# Isolator.net
KiCad netlist of a schematic drawn in Altium Designer
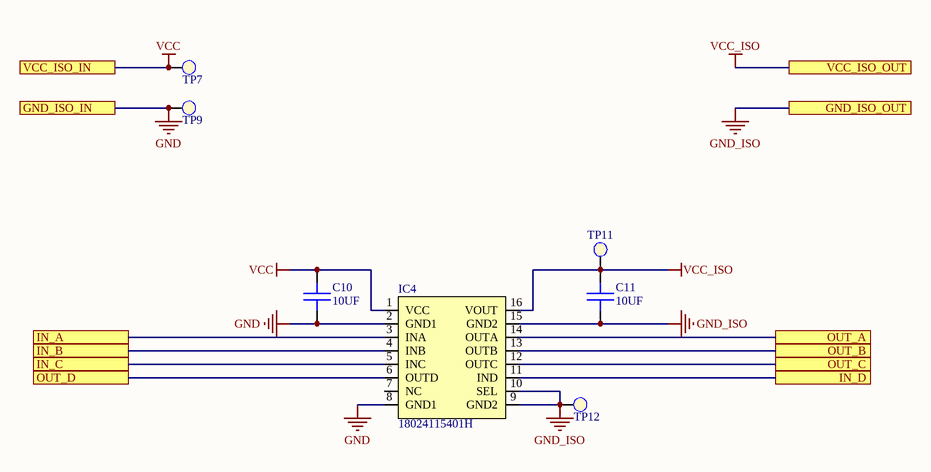
[diagram p0: Isolator.SchDoc]

(export (version "E")
  (design (tool "Eeschema 10.0.6"))
  (components
    (comp (ref "C10")
      (value "10UF")
      (footprint "c1206")
      (description "10UF, 16V, X7R, 1206")
      (fields
        (field (name "MANUFACTURER") "Samsung")
        (field (name "MANUFACTURER PART NUMBER") "CL31B106MOHNNNE")
      )
      (libsource (lib "Capacitor") (part "CL31B106MOHNNNE"))
    )
    (comp (ref "C11")
      (value "10UF")
      (footprint "c1206")
      (description "10UF, 16V, X7R, 1206")
      (fields
        (field (name "MANUFACTURER") "Samsung")
        (field (name "MANUFACTURER PART NUMBER") "CL31B106MOHNNNE")
      )
      (libsource (lib "Capacitor") (part "CL31B106MOHNNNE"))
    )
    (comp (ref "IC4")
      (value "18024115401H")
      (footprint "WPME-CDIP_SOIC-16WB")
      (description "WPME-CDIP Capacitive Digital Isolator Powered")
      (fields (field (name "MANUFACTURER") "Wurth Elektronik"))
      (libsource (lib "IntegratedCircuit") (part "18024115401H"))
    )
    (comp (ref "TP7")
      (value "TestPoint1")
      (footprint "SMD_1mmPoint")
      (description "test ölçüm noktası")
      (fields (field (name "MANUFACTURER") "NO BOM DEVICE"))
      (libsource (lib "Connectors") (part "TestPoint1"))
    )
    (comp (ref "TP9")
      (value "TestPoint1")
      (footprint "SMD_1mmPoint")
      (description "test ölçüm noktası")
      (fields (field (name "MANUFACTURER") "NO BOM DEVICE"))
      (libsource (lib "Connectors") (part "TestPoint1"))
    )
    (comp (ref "TP11")
      (value "TestPoint1")
      (footprint "SMD_1mmPoint")
      (description "test ölçüm noktası")
      (fields (field (name "MANUFACTURER") "NO BOM DEVICE"))
      (libsource (lib "Connectors") (part "TestPoint1"))
    )
    (comp (ref "TP12")
      (value "TestPoint1")
      (footprint "SMD_1mmPoint")
      (description "test ölçüm noktası")
      (fields (field (name "MANUFACTURER") "NO BOM DEVICE"))
      (libsource (lib "Connectors") (part "TestPoint1"))
    )
  )
  (nets
    (net (code "1") (name "/IN_A") (class "Default")
      (node (ref "IC4") (pin "3") (pinfunction "INA_3") (pintype "passive"))
    )
    (net (code "2") (name "/IN_B") (class "Default")
      (node (ref "IC4") (pin "4") (pinfunction "INB_4") (pintype "passive"))
    )
    (net (code "3") (name "/IN_C") (class "Default")
      (node (ref "IC4") (pin "5") (pinfunction "INC_5") (pintype "passive"))
    )
    (net (code "4") (name "/IN_D") (class "Default")
      (node (ref "IC4") (pin "11") (pinfunction "IND_11") (pintype "passive"))
    )
    (net (code "5") (name "/OUT_A") (class "Default")
      (node (ref "IC4") (pin "14") (pinfunction "OUTA_14") (pintype "passive"))
    )
    (net (code "6") (name "/OUT_B") (class "Default")
      (node (ref "IC4") (pin "13") (pinfunction "OUTB_13") (pintype "passive"))
    )
    (net (code "7") (name "/OUT_C") (class "Default")
      (node (ref "IC4") (pin "12") (pinfunction "OUTC_12") (pintype "passive"))
    )
    (net (code "8") (name "/OUT_D") (class "Default")
      (node (ref "IC4") (pin "6") (pinfunction "OUTD_6") (pintype "passive"))
    )
    (net (code "9") (name "GND") (class "Default")
      (node (ref "C10") (pin "1") (pintype "passive"))
      (node (ref "IC4") (pin "2") (pinfunction "GND1_2") (pintype "passive"))
      (node (ref "IC4") (pin "8") (pinfunction "GND1_8") (pintype "passive"))
      (node (ref "TP9") (pin "1") (pinfunction "1_1") (pintype "passive"))
    )
    (net (code "10") (name "GND_ISO") (class "Default")
      (node (ref "C11") (pin "1") (pintype "passive"))
      (node (ref "IC4") (pin "10") (pinfunction "SEL_10") (pintype "passive"))
      (node (ref "IC4") (pin "15") (pinfunction "GND2_15") (pintype "passive"))
      (node (ref "IC4") (pin "9") (pinfunction "GND2_9") (pintype "passive"))
      (node (ref "TP12") (pin "1") (pinfunction "1_1") (pintype "passive"))
    )
    (net (code "11") (name "VCC") (class "Default")
      (node (ref "C10") (pin "2") (pintype "passive"))
      (node (ref "IC4") (pin "1") (pinfunction "VCC_1") (pintype "passive"))
      (node (ref "TP7") (pin "1") (pinfunction "1_1") (pintype "passive"))
    )
    (net (code "12") (name "VCC_ISO") (class "Default")
      (node (ref "C11") (pin "2") (pintype "passive"))
      (node (ref "IC4") (pin "16") (pinfunction "VOUT_16") (pintype "passive"))
      (node (ref "TP11") (pin "1") (pinfunction "1_1") (pintype "passive"))
    )
    (net (code "13") (name "unconnected-(IC4-NC-Pad7)") (class "Default")
      (node (ref "IC4") (pin "7") (pinfunction "NC_7") (pintype "passive"))
    )
  )
)
